# darwin-bp4.net
KiCad netlist of a schematic drawn in EAGLE
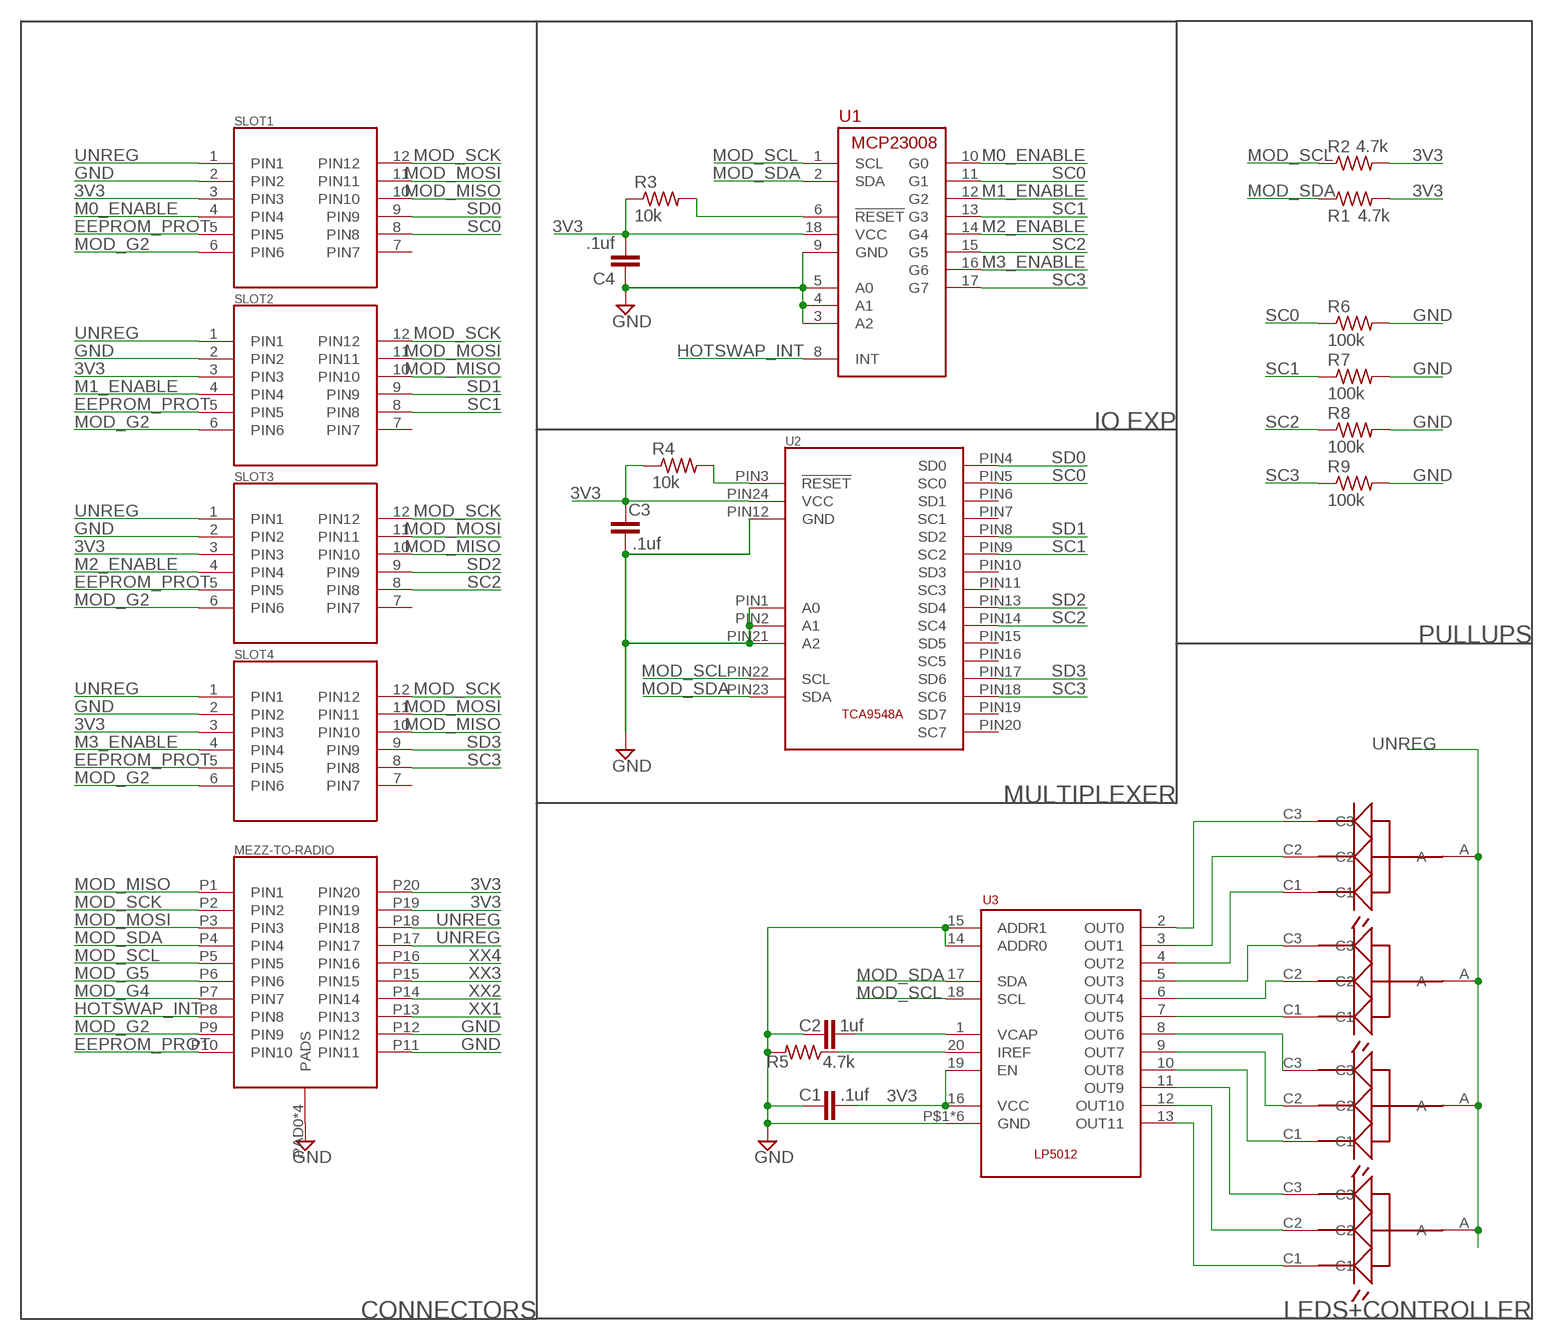
[diagram p0: schematic, sheet 1]

(export (version "E")
  (design (tool "Eeschema 10.0.6"))
  (components
    (comp (ref "C1")
      (value ".1uf")
      (footprint "eagle-import:C0603K")
      (libsource (lib "eagle-import") (part "C-EUC0603K"))
    )
    (comp (ref "C2")
      (value "1uf")
      (footprint "eagle-import:C0603K")
      (libsource (lib "eagle-import") (part "C-EUC0603K"))
    )
    (comp (ref "C3")
      (value ".1uf")
      (footprint "eagle-import:C0603K")
      (libsource (lib "eagle-import") (part "C-EUC0603K"))
    )
    (comp (ref "C4")
      (value ".1uf")
      (footprint "eagle-import:C0603K")
      (libsource (lib "eagle-import") (part "C-EUC0603K"))
    )
    (comp (ref "MEZZ-TO-RADIO")
      (value "M55-6102042R7102(M)")
      (footprint "eagle-import:M55-7102042R")
      (libsource (lib "eagle-import") (part "M55-6102042R7102(M)"))
    )
    (comp (ref "R1")
      (value "4.7k")
      (footprint "eagle-import:R0603")
      (libsource (lib "eagle-import") (part "R-US_R0603"))
    )
    (comp (ref "R2")
      (value "4.7k")
      (footprint "eagle-import:R0603")
      (libsource (lib "eagle-import") (part "R-US_R0603"))
    )
    (comp (ref "R3")
      (value "10k")
      (footprint "eagle-import:R0603")
      (libsource (lib "eagle-import") (part "R-US_R0603"))
    )
    (comp (ref "R4")
      (value "10k")
      (footprint "eagle-import:R0603")
      (libsource (lib "eagle-import") (part "R-US_R0603"))
    )
    (comp (ref "R5")
      (value "4.7k")
      (footprint "eagle-import:R0603")
      (libsource (lib "eagle-import") (part "R-US_R0603"))
    )
    (comp (ref "R6")
      (value "100k")
      (footprint "eagle-import:R0603")
      (libsource (lib "eagle-import") (part "R-US_R0603"))
    )
    (comp (ref "R7")
      (value "100k")
      (footprint "eagle-import:R0603")
      (libsource (lib "eagle-import") (part "R-US_R0603"))
    )
    (comp (ref "R8")
      (value "100k")
      (footprint "eagle-import:R0603")
      (libsource (lib "eagle-import") (part "R-US_R0603"))
    )
    (comp (ref "R9")
      (value "100k")
      (footprint "eagle-import:R0603")
      (libsource (lib "eagle-import") (part "R-US_R0603"))
    )
    (comp (ref "SLOT1")
      (value "2X6-HEADERSDS")
      (footprint "eagle-import:12PH")
      (libsource (lib "eagle-import") (part "2X6-HEADERSDS"))
    )
    (comp (ref "SLOT2")
      (value "2X6-HEADERSDS")
      (footprint "eagle-import:12PH")
      (libsource (lib "eagle-import") (part "2X6-HEADERSDS"))
    )
    (comp (ref "SLOT3")
      (value "2X6-HEADERSDS")
      (footprint "eagle-import:12PH")
      (libsource (lib "eagle-import") (part "2X6-HEADERSDS"))
    )
    (comp (ref "SLOT4")
      (value "2X6-HEADERSDS")
      (footprint "eagle-import:12PH")
      (libsource (lib "eagle-import") (part "2X6-HEADERSDS"))
    )
    (comp (ref "U$1")
      (value "CLMVC-FKC-CGJJM569ABB7A343")
      (footprint "eagle-import:2MMPLCC4")
      (libsource (lib "eagle-import") (part "CLMVC-FKC-CGJJM569ABB7A343"))
    )
    (comp (ref "U$2")
      (value "CLMVC-FKC-CGJJM569ABB7A343")
      (footprint "eagle-import:2MMPLCC4")
      (libsource (lib "eagle-import") (part "CLMVC-FKC-CGJJM569ABB7A343"))
    )
    (comp (ref "U$3")
      (value "CLMVC-FKC-CGJJM569ABB7A343")
      (footprint "eagle-import:2MMPLCC4")
      (libsource (lib "eagle-import") (part "CLMVC-FKC-CGJJM569ABB7A343"))
    )
    (comp (ref "U$4")
      (value "CLMVC-FKC-CGJJM569ABB7A343")
      (footprint "eagle-import:2MMPLCC4")
      (libsource (lib "eagle-import") (part "CLMVC-FKC-CGJJM569ABB7A343"))
    )
    (comp (ref "U1")
      (value "MCP23008")
      (footprint "eagle-import:SOIC18-W")
      (libsource (lib "eagle-import") (part "MCP23008"))
    )
    (comp (ref "U2")
      (value "TCA9548A")
      (footprint "eagle-import:TSSOP-24")
      (libsource (lib "eagle-import") (part "TCA9548A"))
    )
    (comp (ref "U3")
      (value "LP5012")
      (footprint "eagle-import:QFN40P300X300X80-20N")
      (libsource (lib "eagle-import") (part "LP5012"))
    )
  )
  (nets
    (net (code "1") (name "/3V3") (class "Default")
      (node (ref "C1") (pin "2") (pinfunction "2_2") (pintype "passive"))
      (node (ref "C3") (pin "2") (pinfunction "2_2") (pintype "passive"))
      (node (ref "C4") (pin "2") (pinfunction "2_2") (pintype "passive"))
      (node (ref "MEZZ-TO-RADIO") (pin "P19") (pinfunction "PIN19_P19") (pintype "bidirectional"))
      (node (ref "MEZZ-TO-RADIO") (pin "P20") (pinfunction "PIN20_P20") (pintype "bidirectional"))
      (node (ref "R1") (pin "2") (pinfunction "2_2") (pintype "passive"))
      (node (ref "R2") (pin "2") (pinfunction "2_2") (pintype "passive"))
      (node (ref "R3") (pin "1") (pinfunction "1_1") (pintype "passive"))
      (node (ref "R4") (pin "1") (pinfunction "1_1") (pintype "passive"))
      (node (ref "SLOT1") (pin "3") (pinfunction "PIN3_3") (pintype "bidirectional"))
      (node (ref "SLOT2") (pin "3") (pinfunction "PIN3_3") (pintype "bidirectional"))
      (node (ref "SLOT3") (pin "3") (pinfunction "PIN3_3") (pintype "bidirectional"))
      (node (ref "SLOT4") (pin "3") (pinfunction "PIN3_3") (pintype "bidirectional"))
      (node (ref "U1") (pin "18") (pinfunction "VCC_18") (pintype "bidirectional"))
      (node (ref "U2") (pin "PIN24") (pinfunction "VCC_PIN24") (pintype "bidirectional"))
      (node (ref "U3") (pin "16") (pinfunction "VCC_16") (pintype "bidirectional"))
      (node (ref "U3") (pin "19") (pinfunction "EN_19") (pintype "bidirectional"))
    )
    (net (code "2") (name "/EEPROM_PROT") (class "Default")
      (node (ref "MEZZ-TO-RADIO") (pin "P10") (pinfunction "PIN10_P10") (pintype "bidirectional"))
      (node (ref "SLOT1") (pin "5") (pinfunction "PIN5_5") (pintype "bidirectional"))
      (node (ref "SLOT2") (pin "5") (pinfunction "PIN5_5") (pintype "bidirectional"))
      (node (ref "SLOT3") (pin "5") (pinfunction "PIN5_5") (pintype "bidirectional"))
      (node (ref "SLOT4") (pin "5") (pinfunction "PIN5_5") (pintype "bidirectional"))
    )
    (net (code "3") (name "/HOTSWAP_INT") (class "Default")
      (node (ref "MEZZ-TO-RADIO") (pin "P8") (pinfunction "PIN8_P8") (pintype "bidirectional"))
      (node (ref "U1") (pin "8") (pinfunction "INT_8") (pintype "bidirectional"))
    )
    (net (code "4") (name "/M0_ENABLE") (class "Default")
      (node (ref "SLOT1") (pin "4") (pinfunction "PIN4_4") (pintype "bidirectional"))
      (node (ref "U1") (pin "10") (pinfunction "G0_10") (pintype "bidirectional"))
    )
    (net (code "5") (name "/M1_ENABLE") (class "Default")
      (node (ref "SLOT2") (pin "4") (pinfunction "PIN4_4") (pintype "bidirectional"))
      (node (ref "U1") (pin "12") (pinfunction "G2_12") (pintype "bidirectional"))
    )
    (net (code "6") (name "/M2_ENABLE") (class "Default")
      (node (ref "SLOT3") (pin "4") (pinfunction "PIN4_4") (pintype "bidirectional"))
      (node (ref "U1") (pin "14") (pinfunction "G4_14") (pintype "bidirectional"))
    )
    (net (code "7") (name "/M3_ENABLE") (class "Default")
      (node (ref "SLOT4") (pin "4") (pinfunction "PIN4_4") (pintype "bidirectional"))
      (node (ref "U1") (pin "16") (pinfunction "G6_16") (pintype "bidirectional"))
    )
    (net (code "8") (name "/MOD_G2") (class "Default")
      (node (ref "MEZZ-TO-RADIO") (pin "P9") (pinfunction "PIN9_P9") (pintype "bidirectional"))
      (node (ref "SLOT1") (pin "6") (pinfunction "PIN6_6") (pintype "bidirectional"))
      (node (ref "SLOT2") (pin "6") (pinfunction "PIN6_6") (pintype "bidirectional"))
      (node (ref "SLOT3") (pin "6") (pinfunction "PIN6_6") (pintype "bidirectional"))
      (node (ref "SLOT4") (pin "6") (pinfunction "PIN6_6") (pintype "bidirectional"))
    )
    (net (code "9") (name "/MOD_G4") (class "Default")
      (node (ref "MEZZ-TO-RADIO") (pin "P7") (pinfunction "PIN7_P7") (pintype "bidirectional"))
    )
    (net (code "10") (name "/MOD_G5") (class "Default")
      (node (ref "MEZZ-TO-RADIO") (pin "P6") (pinfunction "PIN6_P6") (pintype "bidirectional"))
    )
    (net (code "11") (name "/MOD_MISO") (class "Default")
      (node (ref "MEZZ-TO-RADIO") (pin "P1") (pinfunction "PIN1_P1") (pintype "bidirectional"))
      (node (ref "SLOT1") (pin "10") (pinfunction "PIN10_10") (pintype "bidirectional"))
      (node (ref "SLOT2") (pin "10") (pinfunction "PIN10_10") (pintype "bidirectional"))
      (node (ref "SLOT3") (pin "10") (pinfunction "PIN10_10") (pintype "bidirectional"))
      (node (ref "SLOT4") (pin "10") (pinfunction "PIN10_10") (pintype "bidirectional"))
    )
    (net (code "12") (name "/MOD_MOSI") (class "Default")
      (node (ref "MEZZ-TO-RADIO") (pin "P3") (pinfunction "PIN3_P3") (pintype "bidirectional"))
      (node (ref "SLOT1") (pin "11") (pinfunction "PIN11_11") (pintype "bidirectional"))
      (node (ref "SLOT2") (pin "11") (pinfunction "PIN11_11") (pintype "bidirectional"))
      (node (ref "SLOT3") (pin "11") (pinfunction "PIN11_11") (pintype "bidirectional"))
      (node (ref "SLOT4") (pin "11") (pinfunction "PIN11_11") (pintype "bidirectional"))
    )
    (net (code "13") (name "/MOD_SCK") (class "Default")
      (node (ref "MEZZ-TO-RADIO") (pin "P2") (pinfunction "PIN2_P2") (pintype "bidirectional"))
      (node (ref "SLOT1") (pin "12") (pinfunction "PIN12_12") (pintype "bidirectional"))
      (node (ref "SLOT2") (pin "12") (pinfunction "PIN12_12") (pintype "bidirectional"))
      (node (ref "SLOT3") (pin "12") (pinfunction "PIN12_12") (pintype "bidirectional"))
      (node (ref "SLOT4") (pin "12") (pinfunction "PIN12_12") (pintype "bidirectional"))
    )
    (net (code "14") (name "/MOD_SCL") (class "Default")
      (node (ref "MEZZ-TO-RADIO") (pin "P5") (pinfunction "PIN5_P5") (pintype "bidirectional"))
      (node (ref "R2") (pin "1") (pinfunction "1_1") (pintype "passive"))
      (node (ref "U1") (pin "1") (pinfunction "SCL_1") (pintype "bidirectional"))
      (node (ref "U2") (pin "PIN22") (pinfunction "SCL_PIN22") (pintype "bidirectional"))
      (node (ref "U3") (pin "18") (pinfunction "SCL_18") (pintype "bidirectional"))
    )
    (net (code "15") (name "/MOD_SDA") (class "Default")
      (node (ref "MEZZ-TO-RADIO") (pin "P4") (pinfunction "PIN4_P4") (pintype "bidirectional"))
      (node (ref "R1") (pin "1") (pinfunction "1_1") (pintype "passive"))
      (node (ref "U1") (pin "2") (pinfunction "SDA_2") (pintype "bidirectional"))
      (node (ref "U2") (pin "PIN23") (pinfunction "SDA_PIN23") (pintype "bidirectional"))
      (node (ref "U3") (pin "17") (pinfunction "SDA_17") (pintype "bidirectional"))
    )
    (net (code "16") (name "/SC0") (class "Default")
      (node (ref "R6") (pin "1") (pinfunction "1_1") (pintype "passive"))
      (node (ref "SLOT1") (pin "8") (pinfunction "PIN8_8") (pintype "bidirectional"))
      (node (ref "U1") (pin "11") (pinfunction "G1_11") (pintype "bidirectional"))
      (node (ref "U2") (pin "PIN5") (pinfunction "SC0_PIN5") (pintype "bidirectional"))
    )
    (net (code "17") (name "/SC1") (class "Default")
      (node (ref "R7") (pin "1") (pinfunction "1_1") (pintype "passive"))
      (node (ref "SLOT2") (pin "8") (pinfunction "PIN8_8") (pintype "bidirectional"))
      (node (ref "U1") (pin "13") (pinfunction "G3_13") (pintype "bidirectional"))
      (node (ref "U2") (pin "PIN9") (pinfunction "SC2_PIN9") (pintype "bidirectional"))
    )
    (net (code "18") (name "/SC2") (class "Default")
      (node (ref "R8") (pin "1") (pinfunction "1_1") (pintype "passive"))
      (node (ref "SLOT3") (pin "8") (pinfunction "PIN8_8") (pintype "bidirectional"))
      (node (ref "U1") (pin "15") (pinfunction "G5_15") (pintype "bidirectional"))
      (node (ref "U2") (pin "PIN14") (pinfunction "SC4_PIN14") (pintype "bidirectional"))
    )
    (net (code "19") (name "/SC3") (class "Default")
      (node (ref "R9") (pin "1") (pinfunction "1_1") (pintype "passive"))
      (node (ref "SLOT4") (pin "8") (pinfunction "PIN8_8") (pintype "bidirectional"))
      (node (ref "U1") (pin "17") (pinfunction "G7_17") (pintype "bidirectional"))
      (node (ref "U2") (pin "PIN18") (pinfunction "SC6_PIN18") (pintype "bidirectional"))
    )
    (net (code "20") (name "/SD0") (class "Default")
      (node (ref "SLOT1") (pin "9") (pinfunction "PIN9_9") (pintype "bidirectional"))
      (node (ref "U2") (pin "PIN4") (pinfunction "SD0_PIN4") (pintype "bidirectional"))
    )
    (net (code "21") (name "/SD1") (class "Default")
      (node (ref "SLOT2") (pin "9") (pinfunction "PIN9_9") (pintype "bidirectional"))
      (node (ref "U2") (pin "PIN8") (pinfunction "SD2_PIN8") (pintype "bidirectional"))
    )
    (net (code "22") (name "/SD2") (class "Default")
      (node (ref "SLOT3") (pin "9") (pinfunction "PIN9_9") (pintype "bidirectional"))
      (node (ref "U2") (pin "PIN13") (pinfunction "SD4_PIN13") (pintype "bidirectional"))
    )
    (net (code "23") (name "/SD3") (class "Default")
      (node (ref "SLOT4") (pin "9") (pinfunction "PIN9_9") (pintype "bidirectional"))
      (node (ref "U2") (pin "PIN17") (pinfunction "SD6_PIN17") (pintype "bidirectional"))
    )
    (net (code "24") (name "/UNREG") (class "Default")
      (node (ref "MEZZ-TO-RADIO") (pin "P17") (pinfunction "PIN17_P17") (pintype "bidirectional"))
      (node (ref "MEZZ-TO-RADIO") (pin "P18") (pinfunction "PIN18_P18") (pintype "bidirectional"))
      (node (ref "SLOT1") (pin "1") (pinfunction "PIN1_1") (pintype "bidirectional"))
      (node (ref "SLOT2") (pin "1") (pinfunction "PIN1_1") (pintype "bidirectional"))
      (node (ref "SLOT3") (pin "1") (pinfunction "PIN1_1") (pintype "bidirectional"))
      (node (ref "SLOT4") (pin "1") (pinfunction "PIN1_1") (pintype "bidirectional"))
      (node (ref "U$1") (pin "A") (pinfunction "A_A") (pintype "bidirectional"))
      (node (ref "U$2") (pin "A") (pinfunction "A_A") (pintype "bidirectional"))
      (node (ref "U$3") (pin "A") (pinfunction "A_A") (pintype "bidirectional"))
      (node (ref "U$4") (pin "A") (pinfunction "A_A") (pintype "bidirectional"))
    )
    (net (code "25") (name "/XX1") (class "Default")
      (node (ref "MEZZ-TO-RADIO") (pin "P13") (pinfunction "PIN13_P13") (pintype "bidirectional"))
    )
    (net (code "26") (name "/XX2") (class "Default")
      (node (ref "MEZZ-TO-RADIO") (pin "P14") (pinfunction "PIN14_P14") (pintype "bidirectional"))
    )
    (net (code "27") (name "/XX3") (class "Default")
      (node (ref "MEZZ-TO-RADIO") (pin "P15") (pinfunction "PIN15_P15") (pintype "bidirectional"))
    )
    (net (code "28") (name "/XX4") (class "Default")
      (node (ref "MEZZ-TO-RADIO") (pin "P16") (pinfunction "PIN16_P16") (pintype "bidirectional"))
    )
    (net (code "29") (name "GND") (class "Default")
      (node (ref "C1") (pin "1") (pinfunction "1_1") (pintype "passive"))
      (node (ref "C2") (pin "1") (pinfunction "1_1") (pintype "passive"))
      (node (ref "C3") (pin "1") (pinfunction "1_1") (pintype "passive"))
      (node (ref "C4") (pin "1") (pinfunction "1_1") (pintype "passive"))
      (node (ref "MEZZ-TO-RADIO") (pin "P11") (pinfunction "PIN11_P11") (pintype "bidirectional"))
      (node (ref "MEZZ-TO-RADIO") (pin "P12") (pinfunction "PIN12_P12") (pintype "bidirectional"))
      (node (ref "MEZZ-TO-RADIO") (pin "PAD0") (pinfunction "PADS_PAD0") (pintype "bidirectional"))
      (node (ref "MEZZ-TO-RADIO") (pin "PAD1") (pinfunction "PADS_PAD1") (pintype "bidirectional"))
      (node (ref "MEZZ-TO-RADIO") (pin "PAD2") (pinfunction "PADS_PAD2") (pintype "bidirectional"))
      (node (ref "MEZZ-TO-RADIO") (pin "PAD3") (pinfunction "PADS_PAD3") (pintype "bidirectional"))
      (node (ref "R5") (pin "2") (pinfunction "2_2") (pintype "passive"))
      (node (ref "R6") (pin "2") (pinfunction "2_2") (pintype "passive"))
      (node (ref "R7") (pin "2") (pinfunction "2_2") (pintype "passive"))
      (node (ref "R8") (pin "2") (pinfunction "2_2") (pintype "passive"))
      (node (ref "R9") (pin "2") (pinfunction "2_2") (pintype "passive"))
      (node (ref "SLOT1") (pin "2") (pinfunction "PIN2_2") (pintype "bidirectional"))
      (node (ref "SLOT2") (pin "2") (pinfunction "PIN2_2") (pintype "bidirectional"))
      (node (ref "SLOT3") (pin "2") (pinfunction "PIN2_2") (pintype "bidirectional"))
      (node (ref "SLOT4") (pin "2") (pinfunction "PIN2_2") (pintype "bidirectional"))
      (node (ref "U1") (pin "3") (pinfunction "A2_3") (pintype "bidirectional"))
      (node (ref "U1") (pin "4") (pinfunction "A1_4") (pintype "bidirectional"))
      (node (ref "U1") (pin "5") (pinfunction "A0_5") (pintype "bidirectional"))
      (node (ref "U1") (pin "9") (pinfunction "GND_9") (pintype "bidirectional"))
      (node (ref "U2") (pin "PIN1") (pinfunction "A0_PIN1") (pintype "bidirectional"))
      (node (ref "U2") (pin "PIN12") (pinfunction "GND_PIN12") (pintype "bidirectional"))
      (node (ref "U2") (pin "PIN2") (pinfunction "A1_PIN2") (pintype "bidirectional"))
      (node (ref "U2") (pin "PIN21") (pinfunction "A2_PIN21") (pintype "bidirectional"))
      (node (ref "U3") (pin "14") (pinfunction "ADDR0_14") (pintype "bidirectional"))
      (node (ref "U3") (pin "15") (pinfunction "ADDR1_15") (pintype "bidirectional"))
      (node (ref "U3") (pin "P$1") (pinfunction "GND_P$1") (pintype "bidirectional"))
      (node (ref "U3") (pin "P$2") (pinfunction "GND_P$2") (pintype "bidirectional"))
      (node (ref "U3") (pin "P$3") (pinfunction "GND_P$3") (pintype "bidirectional"))
      (node (ref "U3") (pin "P$4") (pinfunction "GND_P$4") (pintype "bidirectional"))
      (node (ref "U3") (pin "P$5") (pinfunction "GND_P$5") (pintype "bidirectional"))
      (node (ref "U3") (pin "P$6") (pinfunction "GND_P$6") (pintype "bidirectional"))
    )
    (net (code "30") (name "Net-(U1-~{RESET})") (class "Default")
      (node (ref "R3") (pin "2") (pinfunction "2_2") (pintype "passive"))
      (node (ref "U1") (pin "6") (pinfunction "~{RESET}_6") (pintype "bidirectional"))
    )
    (net (code "31") (name "Net-(U2-~{RESET})") (class "Default")
      (node (ref "R4") (pin "2") (pinfunction "2_2") (pintype "passive"))
      (node (ref "U2") (pin "PIN3") (pinfunction "~{RESET}_PIN3") (pintype "bidirectional"))
    )
    (net (code "32") (name "Net-(U3-IREF)") (class "Default")
      (node (ref "R5") (pin "1") (pinfunction "1_1") (pintype "passive"))
      (node (ref "U3") (pin "20") (pinfunction "IREF_20") (pintype "bidirectional"))
    )
    (net (code "33") (name "Net-(U3-OUT0)") (class "Default")
      (node (ref "U$1") (pin "C3") (pinfunction "C3_C3") (pintype "bidirectional"))
      (node (ref "U3") (pin "2") (pinfunction "OUT0_2") (pintype "bidirectional"))
    )
    (net (code "34") (name "Net-(U3-OUT1)") (class "Default")
      (node (ref "U$1") (pin "C2") (pinfunction "C2_C2") (pintype "bidirectional"))
      (node (ref "U3") (pin "3") (pinfunction "OUT1_3") (pintype "bidirectional"))
    )
    (net (code "35") (name "Net-(U3-OUT2)") (class "Default")
      (node (ref "U$1") (pin "C1") (pinfunction "C1_C1") (pintype "bidirectional"))
      (node (ref "U3") (pin "4") (pinfunction "OUT2_4") (pintype "bidirectional"))
    )
    (net (code "36") (name "Net-(U3-OUT3)") (class "Default")
      (node (ref "U$2") (pin "C3") (pinfunction "C3_C3") (pintype "bidirectional"))
      (node (ref "U3") (pin "5") (pinfunction "OUT3_5") (pintype "bidirectional"))
    )
    (net (code "37") (name "Net-(U3-OUT4)") (class "Default")
      (node (ref "U$2") (pin "C2") (pinfunction "C2_C2") (pintype "bidirectional"))
      (node (ref "U3") (pin "6") (pinfunction "OUT4_6") (pintype "bidirectional"))
    )
    (net (code "38") (name "Net-(U3-OUT5)") (class "Default")
      (node (ref "U$2") (pin "C1") (pinfunction "C1_C1") (pintype "bidirectional"))
      (node (ref "U3") (pin "7") (pinfunction "OUT5_7") (pintype "bidirectional"))
    )
    (net (code "39") (name "Net-(U3-OUT6)") (class "Default")
      (node (ref "U$3") (pin "C3") (pinfunction "C3_C3") (pintype "bidirectional"))
      (node (ref "U3") (pin "8") (pinfunction "OUT6_8") (pintype "bidirectional"))
    )
    (net (code "40") (name "Net-(U3-OUT7)") (class "Default")
      (node (ref "U$3") (pin "C2") (pinfunction "C2_C2") (pintype "bidirectional"))
      (node (ref "U3") (pin "9") (pinfunction "OUT7_9") (pintype "bidirectional"))
    )
    (net (code "41") (name "Net-(U3-OUT8)") (class "Default")
      (node (ref "U$3") (pin "C1") (pinfunction "C1_C1") (pintype "bidirectional"))
      (node (ref "U3") (pin "10") (pinfunction "OUT8_10") (pintype "bidirectional"))
    )
    (net (code "42") (name "Net-(U3-OUT9)") (class "Default")
      (node (ref "U$4") (pin "C3") (pinfunction "C3_C3") (pintype "bidirectional"))
      (node (ref "U3") (pin "11") (pinfunction "OUT9_11") (pintype "bidirectional"))
    )
    (net (code "43") (name "Net-(U3-OUT10)") (class "Default")
      (node (ref "U$4") (pin "C2") (pinfunction "C2_C2") (pintype "bidirectional"))
      (node (ref "U3") (pin "12") (pinfunction "OUT10_12") (pintype "bidirectional"))
    )
    (net (code "44") (name "Net-(U3-OUT11)") (class "Default")
      (node (ref "U$4") (pin "C1") (pinfunction "C1_C1") (pintype "bidirectional"))
      (node (ref "U3") (pin "13") (pinfunction "OUT11_13") (pintype "bidirectional"))
    )
    (net (code "45") (name "Net-(U3-VCAP)") (class "Default")
      (node (ref "C2") (pin "2") (pinfunction "2_2") (pintype "passive"))
      (node (ref "U3") (pin "1") (pinfunction "VCAP_1") (pintype "bidirectional"))
    )
    (net (code "46") (name "unconnected-(SLOT1-PIN7-Pad7)") (class "Default")
      (node (ref "SLOT1") (pin "7") (pinfunction "PIN7_7") (pintype "bidirectional"))
    )
    (net (code "47") (name "unconnected-(SLOT2-PIN7-Pad7)") (class "Default")
      (node (ref "SLOT2") (pin "7") (pinfunction "PIN7_7") (pintype "bidirectional"))
    )
    (net (code "48") (name "unconnected-(SLOT3-PIN7-Pad7)") (class "Default")
      (node (ref "SLOT3") (pin "7") (pinfunction "PIN7_7") (pintype "bidirectional"))
    )
    (net (code "49") (name "unconnected-(SLOT4-PIN7-Pad7)") (class "Default")
      (node (ref "SLOT4") (pin "7") (pinfunction "PIN7_7") (pintype "bidirectional"))
    )
    (net (code "50") (name "unconnected-(U2-SC1-PadPIN7)") (class "Default")
      (node (ref "U2") (pin "PIN7") (pinfunction "SC1_PIN7") (pintype "bidirectional"))
    )
    (net (code "51") (name "unconnected-(U2-SC3-PadPIN11)") (class "Default")
      (node (ref "U2") (pin "PIN11") (pinfunction "SC3_PIN11") (pintype "bidirectional"))
    )
    (net (code "52") (name "unconnected-(U2-SC5-PadPIN16)") (class "Default")
      (node (ref "U2") (pin "PIN16") (pinfunction "SC5_PIN16") (pintype "bidirectional"))
    )
    (net (code "53") (name "unconnected-(U2-SC7-PadPIN20)") (class "Default")
      (node (ref "U2") (pin "PIN20") (pinfunction "SC7_PIN20") (pintype "bidirectional"))
    )
    (net (code "54") (name "unconnected-(U2-SD1-PadPIN6)") (class "Default")
      (node (ref "U2") (pin "PIN6") (pinfunction "SD1_PIN6") (pintype "bidirectional"))
    )
    (net (code "55") (name "unconnected-(U2-SD3-PadPIN10)") (class "Default")
      (node (ref "U2") (pin "PIN10") (pinfunction "SD3_PIN10") (pintype "bidirectional"))
    )
    (net (code "56") (name "unconnected-(U2-SD5-PadPIN15)") (class "Default")
      (node (ref "U2") (pin "PIN15") (pinfunction "SD5_PIN15") (pintype "bidirectional"))
    )
    (net (code "57") (name "unconnected-(U2-SD7-PadPIN19)") (class "Default")
      (node (ref "U2") (pin "PIN19") (pinfunction "SD7_PIN19") (pintype "bidirectional"))
    )
  )
)
